# Project_Tango.net
KiCad netlist of a schematic drawn in EAGLE
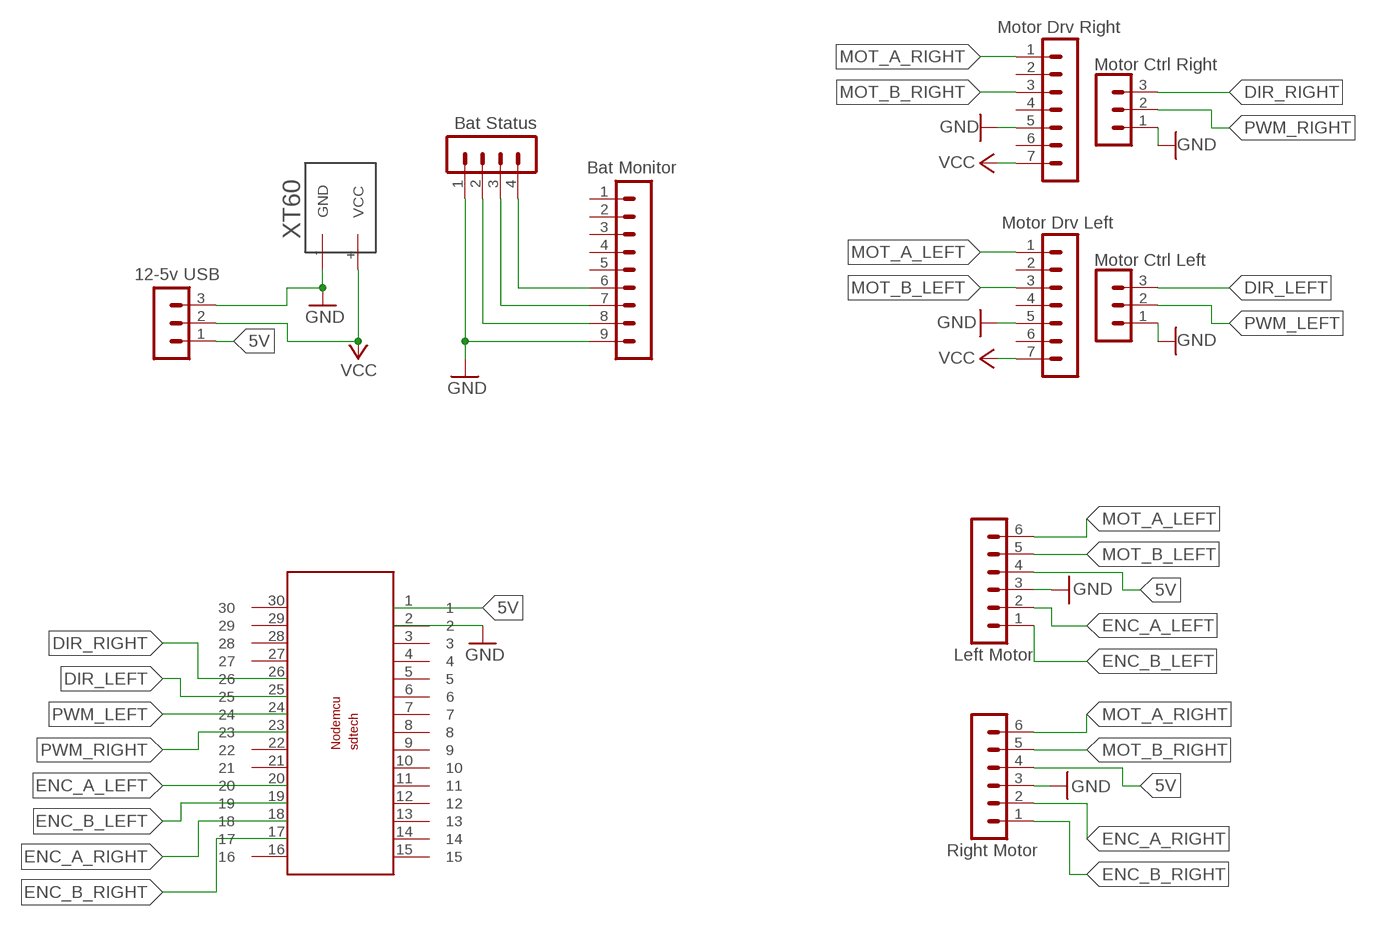
[diagram p0: schematic, sheet 1]

(export (version "E")
  (design (tool "Eeschema 10.0.6"))
  (components
    (comp (ref "BAT_MONITOR")
      (value "Bat Monitor")
      (footprint "eagle-import:MA09-1")
      (libsource (lib "eagle-import") (part "MA09-1"))
    )
    (comp (ref "BAT_STATUS")
      (value "Bat Status")
      (footprint "eagle-import:MA04-1")
      (libsource (lib "eagle-import") (part "MA04-1"))
    )
    (comp (ref "LEFTMOTOR")
      (value "Left Motor")
      (footprint "eagle-import:MA06-1")
      (libsource (lib "eagle-import") (part "MA06-1"))
    )
    (comp (ref "MOTORDRV_RIGHT")
      (value "Motor Drv Right")
      (footprint "eagle-import:MA07-1")
      (libsource (lib "eagle-import") (part "MA07-1"))
    )
    (comp (ref "SV1")
      (value "12-5v USB")
      (footprint "eagle-import:MA03-1")
      (libsource (lib "eagle-import") (part "MA03-1"))
    )
    (comp (ref "SV2")
      (value "Right Motor")
      (footprint "eagle-import:MA06-1")
      (libsource (lib "eagle-import") (part "MA06-1"))
    )
    (comp (ref "SV3")
      (value "Motor Drv Left")
      (footprint "eagle-import:MA07-1")
      (libsource (lib "eagle-import") (part "MA07-1"))
    )
    (comp (ref "SV5")
      (value "Motor Ctrl Right")
      (footprint "eagle-import:MA03-1")
      (libsource (lib "eagle-import") (part "MA03-1"))
    )
    (comp (ref "SV6")
      (value "Motor Ctrl Left")
      (footprint "eagle-import:MA03-1")
      (libsource (lib "eagle-import") (part "MA03-1"))
    )
    (comp (ref "U$1")
      (value "Node MCU")
      (footprint "eagle-import:NODEMCUESP8266")
      (libsource (lib "eagle-import") (part "NODEMCUESP8266"))
    )
    (comp (ref "U$2")
      (value "XT60")
      (footprint "eagle-import:XT60")
      (libsource (lib "eagle-import") (part "XT60"))
    )
  )
  (nets
    (net (code "1") (name "5V") (class "Default")
      (node (ref "LEFTMOTOR") (pin "4") (pinfunction "4_4") (pintype "passive"))
      (node (ref "SV1") (pin "1") (pinfunction "1_1") (pintype "passive"))
      (node (ref "SV2") (pin "4") (pinfunction "4_4") (pintype "passive"))
      (node (ref "U$1") (pin "1") (pinfunction "1_1") (pintype "bidirectional"))
    )
    (net (code "2") (name "DIR_LEFT") (class "Default")
      (node (ref "SV6") (pin "3") (pinfunction "3_3") (pintype "passive"))
      (node (ref "U$1") (pin "25") (pinfunction "25_25") (pintype "bidirectional"))
    )
    (net (code "3") (name "DIR_RIGHT") (class "Default")
      (node (ref "SV5") (pin "3") (pinfunction "3_3") (pintype "passive"))
      (node (ref "U$1") (pin "26") (pinfunction "26_26") (pintype "bidirectional"))
    )
    (net (code "4") (name "ENC_A_LEFT") (class "Default")
      (node (ref "LEFTMOTOR") (pin "2") (pinfunction "2_2") (pintype "passive"))
      (node (ref "U$1") (pin "20") (pinfunction "20_20") (pintype "bidirectional"))
    )
    (net (code "5") (name "ENC_A_RIGHT") (class "Default")
      (node (ref "SV2") (pin "2") (pinfunction "2_2") (pintype "passive"))
      (node (ref "U$1") (pin "18") (pinfunction "18_18") (pintype "bidirectional"))
    )
    (net (code "6") (name "ENC_B_LEFT") (class "Default")
      (node (ref "LEFTMOTOR") (pin "1") (pinfunction "1_1") (pintype "passive"))
      (node (ref "U$1") (pin "19") (pinfunction "19_19") (pintype "bidirectional"))
    )
    (net (code "7") (name "ENC_B_RIGHT") (class "Default")
      (node (ref "SV2") (pin "1") (pinfunction "1_1") (pintype "passive"))
      (node (ref "U$1") (pin "17") (pinfunction "17_17") (pintype "bidirectional"))
    )
    (net (code "8") (name "GND") (class "Default")
      (node (ref "BAT_MONITOR") (pin "9") (pinfunction "9_9") (pintype "passive"))
      (node (ref "BAT_STATUS") (pin "1") (pinfunction "1_1") (pintype "passive"))
      (node (ref "LEFTMOTOR") (pin "3") (pinfunction "3_3") (pintype "passive"))
      (node (ref "MOTORDRV_RIGHT") (pin "5") (pinfunction "5_5") (pintype "passive"))
      (node (ref "SV1") (pin "3") (pinfunction "3_3") (pintype "passive"))
      (node (ref "SV2") (pin "3") (pinfunction "3_3") (pintype "passive"))
      (node (ref "SV3") (pin "5") (pinfunction "5_5") (pintype "passive"))
      (node (ref "SV5") (pin "1") (pinfunction "1_1") (pintype "passive"))
      (node (ref "SV6") (pin "1") (pinfunction "1_1") (pintype "passive"))
      (node (ref "U$1") (pin "2") (pinfunction "2_2") (pintype "bidirectional"))
      (node (ref "U$2") (pin "-") (pinfunction "GND_-") (pintype "bidirectional"))
    )
    (net (code "9") (name "MOT_A_LEFT") (class "Default")
      (node (ref "LEFTMOTOR") (pin "6") (pinfunction "6_6") (pintype "passive"))
      (node (ref "SV3") (pin "1") (pinfunction "1_1") (pintype "passive"))
    )
    (net (code "10") (name "MOT_A_RIGHT") (class "Default")
      (node (ref "MOTORDRV_RIGHT") (pin "1") (pinfunction "1_1") (pintype "passive"))
      (node (ref "SV2") (pin "6") (pinfunction "6_6") (pintype "passive"))
    )
    (net (code "11") (name "MOT_B_LEFT") (class "Default")
      (node (ref "LEFTMOTOR") (pin "5") (pinfunction "5_5") (pintype "passive"))
      (node (ref "SV3") (pin "3") (pinfunction "3_3") (pintype "passive"))
    )
    (net (code "12") (name "MOT_B_RIGHT") (class "Default")
      (node (ref "MOTORDRV_RIGHT") (pin "3") (pinfunction "3_3") (pintype "passive"))
      (node (ref "SV2") (pin "5") (pinfunction "5_5") (pintype "passive"))
    )
    (net (code "13") (name "Net-(BAT_MONITOR-Pad6)") (class "Default")
      (node (ref "BAT_MONITOR") (pin "6") (pinfunction "6_6") (pintype "passive"))
      (node (ref "BAT_STATUS") (pin "4") (pinfunction "4_4") (pintype "passive"))
    )
    (net (code "14") (name "Net-(BAT_MONITOR-Pad7)") (class "Default")
      (node (ref "BAT_MONITOR") (pin "7") (pinfunction "7_7") (pintype "passive"))
      (node (ref "BAT_STATUS") (pin "3") (pinfunction "3_3") (pintype "passive"))
    )
    (net (code "15") (name "Net-(BAT_MONITOR-Pad8)") (class "Default")
      (node (ref "BAT_MONITOR") (pin "8") (pinfunction "8_8") (pintype "passive"))
      (node (ref "BAT_STATUS") (pin "2") (pinfunction "2_2") (pintype "passive"))
    )
    (net (code "16") (name "PWM_LEFT") (class "Default")
      (node (ref "SV6") (pin "2") (pinfunction "2_2") (pintype "passive"))
      (node (ref "U$1") (pin "24") (pinfunction "24_24") (pintype "bidirectional"))
    )
    (net (code "17") (name "PWM_RIGHT") (class "Default")
      (node (ref "SV5") (pin "2") (pinfunction "2_2") (pintype "passive"))
      (node (ref "U$1") (pin "23") (pinfunction "23_23") (pintype "bidirectional"))
    )
    (net (code "18") (name "VCC") (class "Default")
      (node (ref "MOTORDRV_RIGHT") (pin "7") (pinfunction "7_7") (pintype "passive"))
      (node (ref "SV1") (pin "2") (pinfunction "2_2") (pintype "passive"))
      (node (ref "SV3") (pin "7") (pinfunction "7_7") (pintype "passive"))
      (node (ref "U$2") (pin "+") (pinfunction "VCC_+") (pintype "bidirectional"))
    )
    (net (code "19") (name "unconnected-(BAT_MONITOR-Pad1)") (class "Default")
      (node (ref "BAT_MONITOR") (pin "1") (pinfunction "1_1") (pintype "passive"))
    )
    (net (code "20") (name "unconnected-(BAT_MONITOR-Pad2)") (class "Default")
      (node (ref "BAT_MONITOR") (pin "2") (pinfunction "2_2") (pintype "passive"))
    )
    (net (code "21") (name "unconnected-(BAT_MONITOR-Pad3)") (class "Default")
      (node (ref "BAT_MONITOR") (pin "3") (pinfunction "3_3") (pintype "passive"))
    )
    (net (code "22") (name "unconnected-(BAT_MONITOR-Pad4)") (class "Default")
      (node (ref "BAT_MONITOR") (pin "4") (pinfunction "4_4") (pintype "passive"))
    )
    (net (code "23") (name "unconnected-(BAT_MONITOR-Pad5)") (class "Default")
      (node (ref "BAT_MONITOR") (pin "5") (pinfunction "5_5") (pintype "passive"))
    )
    (net (code "24") (name "unconnected-(MOTORDRV_RIGHT-Pad2)") (class "Default")
      (node (ref "MOTORDRV_RIGHT") (pin "2") (pinfunction "2_2") (pintype "passive"))
    )
    (net (code "25") (name "unconnected-(MOTORDRV_RIGHT-Pad4)") (class "Default")
      (node (ref "MOTORDRV_RIGHT") (pin "4") (pinfunction "4_4") (pintype "passive"))
    )
    (net (code "26") (name "unconnected-(MOTORDRV_RIGHT-Pad6)") (class "Default")
      (node (ref "MOTORDRV_RIGHT") (pin "6") (pinfunction "6_6") (pintype "passive"))
    )
    (net (code "27") (name "unconnected-(SV3-Pad2)") (class "Default")
      (node (ref "SV3") (pin "2") (pinfunction "2_2") (pintype "passive"))
    )
    (net (code "28") (name "unconnected-(SV3-Pad4)") (class "Default")
      (node (ref "SV3") (pin "4") (pinfunction "4_4") (pintype "passive"))
    )
    (net (code "29") (name "unconnected-(SV3-Pad6)") (class "Default")
      (node (ref "SV3") (pin "6") (pinfunction "6_6") (pintype "passive"))
    )
    (net (code "30") (name "unconnected-(U$1-Pad3)") (class "Default")
      (node (ref "U$1") (pin "3") (pinfunction "3_3") (pintype "bidirectional"))
    )
    (net (code "31") (name "unconnected-(U$1-Pad4)") (class "Default")
      (node (ref "U$1") (pin "4") (pinfunction "4_4") (pintype "bidirectional"))
    )
    (net (code "32") (name "unconnected-(U$1-Pad5)") (class "Default")
      (node (ref "U$1") (pin "5") (pinfunction "5_5") (pintype "bidirectional"))
    )
    (net (code "33") (name "unconnected-(U$1-Pad6)") (class "Default")
      (node (ref "U$1") (pin "6") (pinfunction "6_6") (pintype "bidirectional"))
    )
    (net (code "34") (name "unconnected-(U$1-Pad7)") (class "Default")
      (node (ref "U$1") (pin "7") (pinfunction "7_7") (pintype "bidirectional"))
    )
    (net (code "35") (name "unconnected-(U$1-Pad8)") (class "Default")
      (node (ref "U$1") (pin "8") (pinfunction "8_8") (pintype "bidirectional"))
    )
    (net (code "36") (name "unconnected-(U$1-Pad9)") (class "Default")
      (node (ref "U$1") (pin "9") (pinfunction "9_9") (pintype "bidirectional"))
    )
    (net (code "37") (name "unconnected-(U$1-Pad10)") (class "Default")
      (node (ref "U$1") (pin "10") (pinfunction "10_10") (pintype "bidirectional"))
    )
    (net (code "38") (name "unconnected-(U$1-Pad11)") (class "Default")
      (node (ref "U$1") (pin "11") (pinfunction "11_11") (pintype "bidirectional"))
    )
    (net (code "39") (name "unconnected-(U$1-Pad12)") (class "Default")
      (node (ref "U$1") (pin "12") (pinfunction "12_12") (pintype "bidirectional"))
    )
    (net (code "40") (name "unconnected-(U$1-Pad13)") (class "Default")
      (node (ref "U$1") (pin "13") (pinfunction "13_13") (pintype "bidirectional"))
    )
    (net (code "41") (name "unconnected-(U$1-Pad14)") (class "Default")
      (node (ref "U$1") (pin "14") (pinfunction "14_14") (pintype "bidirectional"))
    )
    (net (code "42") (name "unconnected-(U$1-Pad15)") (class "Default")
      (node (ref "U$1") (pin "15") (pinfunction "15_15") (pintype "bidirectional"))
    )
    (net (code "43") (name "unconnected-(U$1-Pad16)") (class "Default")
      (node (ref "U$1") (pin "16") (pinfunction "16_16") (pintype "bidirectional"))
    )
    (net (code "44") (name "unconnected-(U$1-Pad21)") (class "Default")
      (node (ref "U$1") (pin "21") (pinfunction "21_21") (pintype "bidirectional"))
    )
    (net (code "45") (name "unconnected-(U$1-Pad22)") (class "Default")
      (node (ref "U$1") (pin "22") (pinfunction "22_22") (pintype "bidirectional"))
    )
    (net (code "46") (name "unconnected-(U$1-Pad27)") (class "Default")
      (node (ref "U$1") (pin "27") (pinfunction "27_27") (pintype "bidirectional"))
    )
    (net (code "47") (name "unconnected-(U$1-Pad28)") (class "Default")
      (node (ref "U$1") (pin "28") (pinfunction "28_28") (pintype "bidirectional"))
    )
    (net (code "48") (name "unconnected-(U$1-Pad29)") (class "Default")
      (node (ref "U$1") (pin "29") (pinfunction "29_29") (pintype "bidirectional"))
    )
    (net (code "49") (name "unconnected-(U$1-Pad30)") (class "Default")
      (node (ref "U$1") (pin "30") (pinfunction "30_30") (pintype "bidirectional"))
    )
  )
)
